# no_erc.net
KiCad netlist of a schematic drawn in Altium Designer
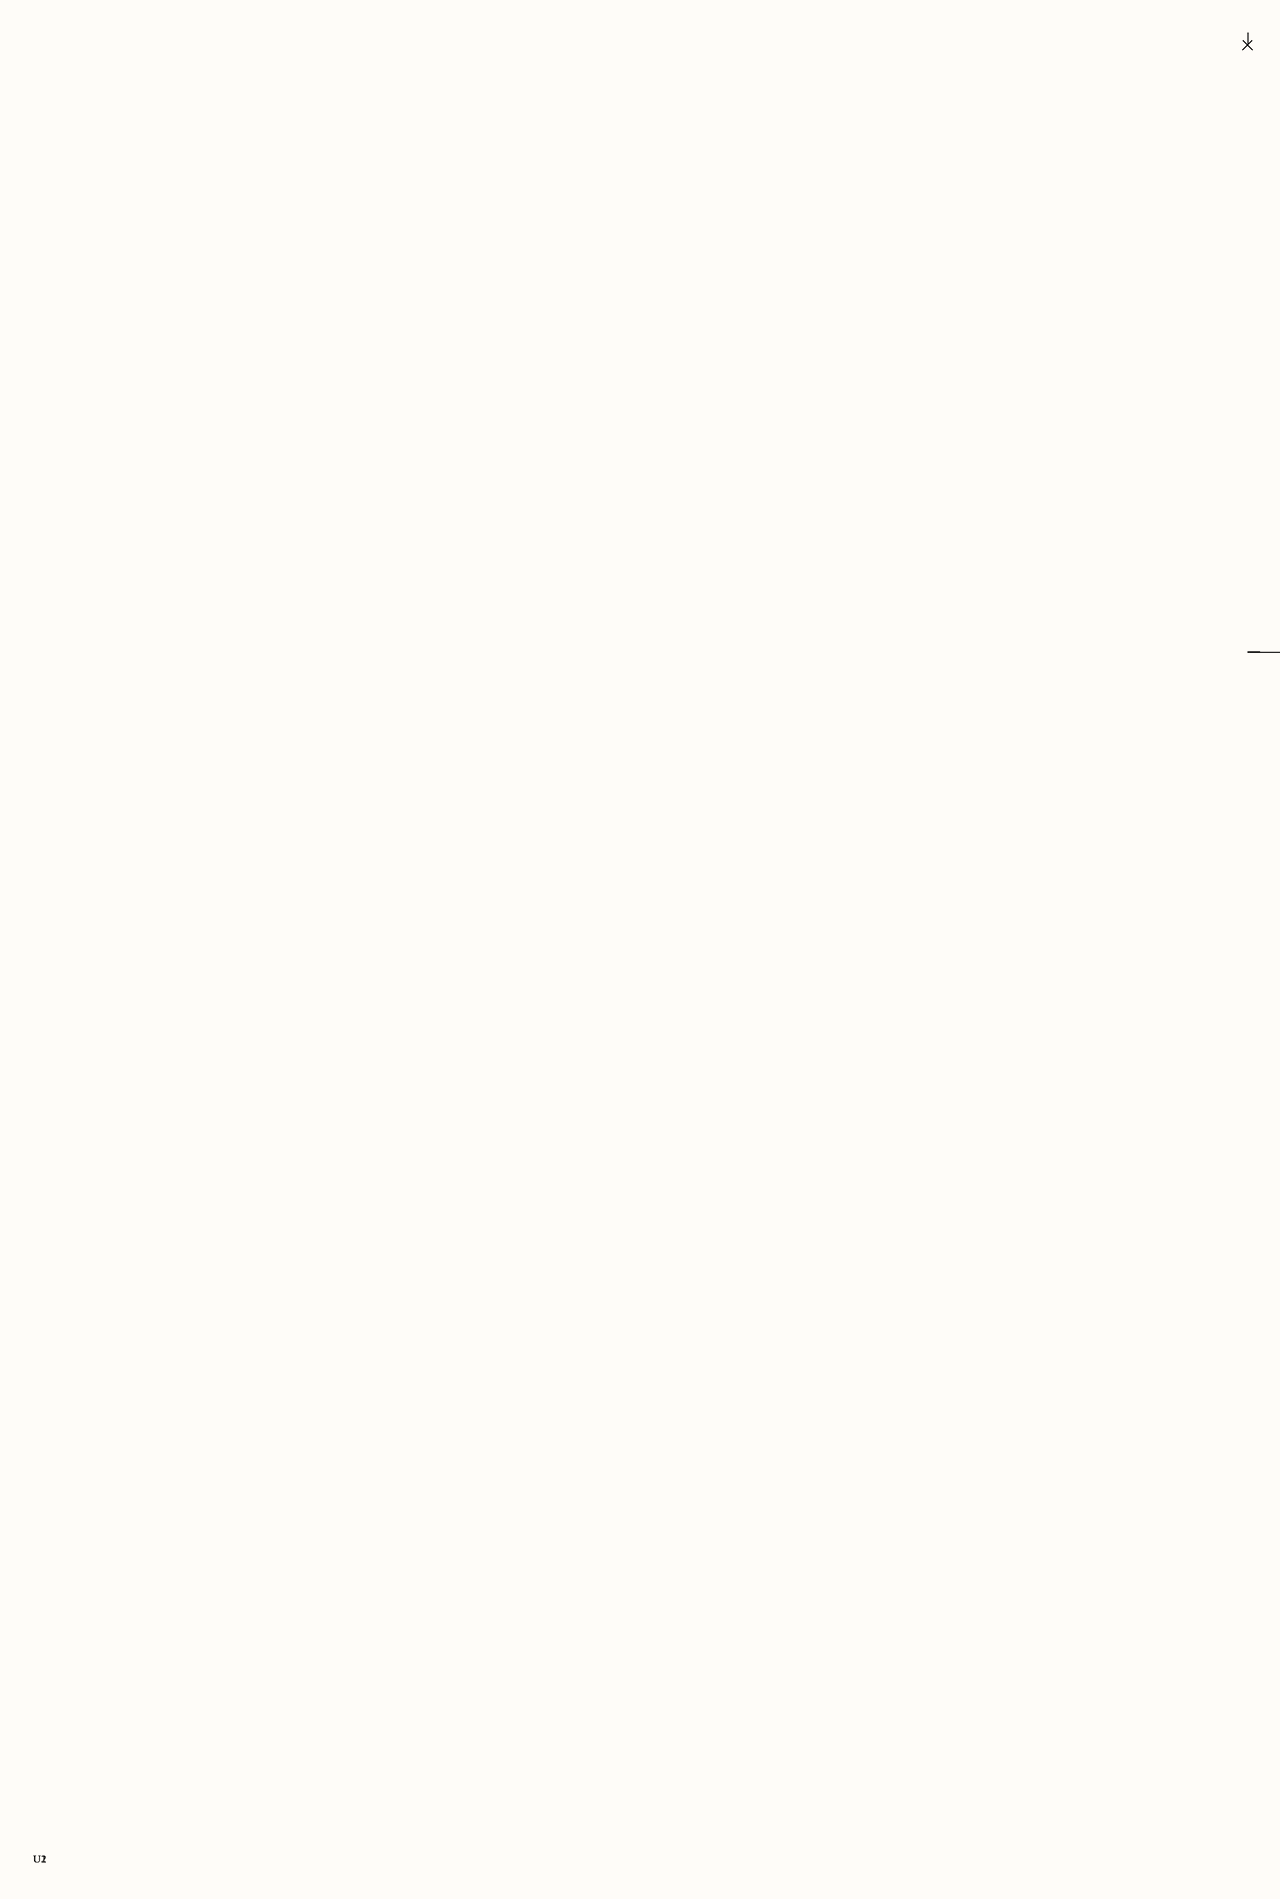
[diagram p0: no_erc.SchDoc, left]
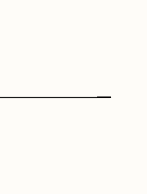
[diagram p1: no_erc.SchDoc, right]

(export (version "E")
  (design (tool "Eeschema 10.0.6"))
  (components
    (comp (ref "U1") (value "~") (libsource (lib "altium-import") (part "root_0_DEVICE_")))
    (comp (ref "U2") (value "~") (libsource (lib "") (part "root_0_DEVICE__1")))
  )
  (nets
    (net (code "1") (name "Net-(U1-A)") (class "Default")
      (node (ref "U1") (pin "1") (pinfunction "A_1") (pintype "passive"))
      (node (ref "U2") (pin "1") (pinfunction "B_1") (pintype "passive"))
    )
    (net (code "2") (name "unconnected-(U1-NC-Pad2)") (class "Default")
      (node (ref "U1") (pin "2") (pinfunction "NC_2") (pintype "passive+no_connect"))
    )
  )
)
